# MR_UartConnector.net
KiCad netlist of a schematic drawn in Altium Designer
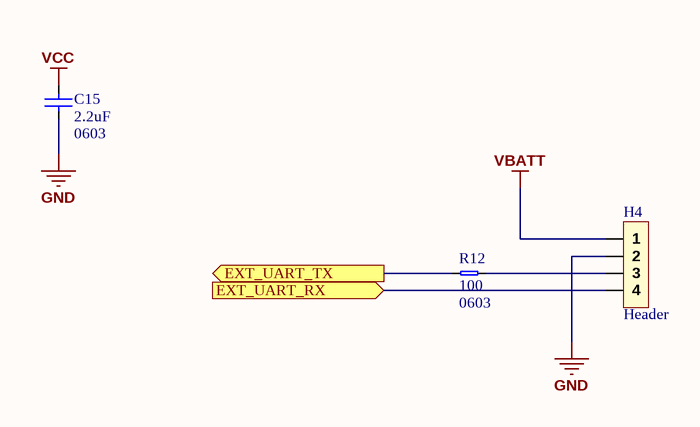
[diagram p0: MR_UartConnector.SchDoc]

(export (version "E")
  (design (tool "Eeschema 10.0.6"))
  (components
    (comp (ref "C15")
      (value "2.2uF")
      (footprint "0603_CAP_LD")
      (description "Ceramic Capacitor")
      (fields (field (name "PACKAGE") "0603") (field (name "Comment") "CerCap"))
      (libsource (lib "MiniRobot") (part "CerCap"))
    )
    (comp (ref "H4")
      (value "Header")
      (footprint "HE14 1x4 Straight")
      (description "Header 4x1 PIns")
      (libsource (lib "MiniRobot") (part "Header_4x1"))
    )
    (comp (ref "R12")
      (value "100")
      (footprint "0603_RES_LD")
      (description "Resistor")
      (fields (field (name "PACKAGE") "0603"))
      (libsource (lib "MiniRobot") (part "Resistor"))
    )
  )
  (nets
    (net (code "1") (name "/EXT_UART_RX") (class "Default")
      (node (ref "H4") (pin "4") (pinfunction "4_4") (pintype "passive"))
    )
    (net (code "2") (name "/EXT_UART_TX") (class "Default")
      (node (ref "R12") (pin "1") (pinfunction "1_1") (pintype "passive"))
    )
    (net (code "3") (name "GND") (class "Default")
      (node (ref "C15") (pin "1") (pinfunction "1_1") (pintype "passive"))
      (node (ref "H4") (pin "2") (pinfunction "2_2") (pintype "passive"))
    )
    (net (code "4") (name "Net-(H4-Pad3)") (class "Default")
      (node (ref "H4") (pin "3") (pinfunction "3_3") (pintype "passive"))
      (node (ref "R12") (pin "2") (pinfunction "2_2") (pintype "passive"))
    )
    (net (code "5") (name "VBATT") (class "Default")
      (node (ref "H4") (pin "1") (pinfunction "1_1") (pintype "passive"))
    )
    (net (code "6") (name "VCC") (class "Default")
      (node (ref "C15") (pin "2") (pinfunction "2_2") (pintype "passive"))
    )
  )
)
